# dr1_h.net
KiCad netlist of a schematic drawn in EAGLE
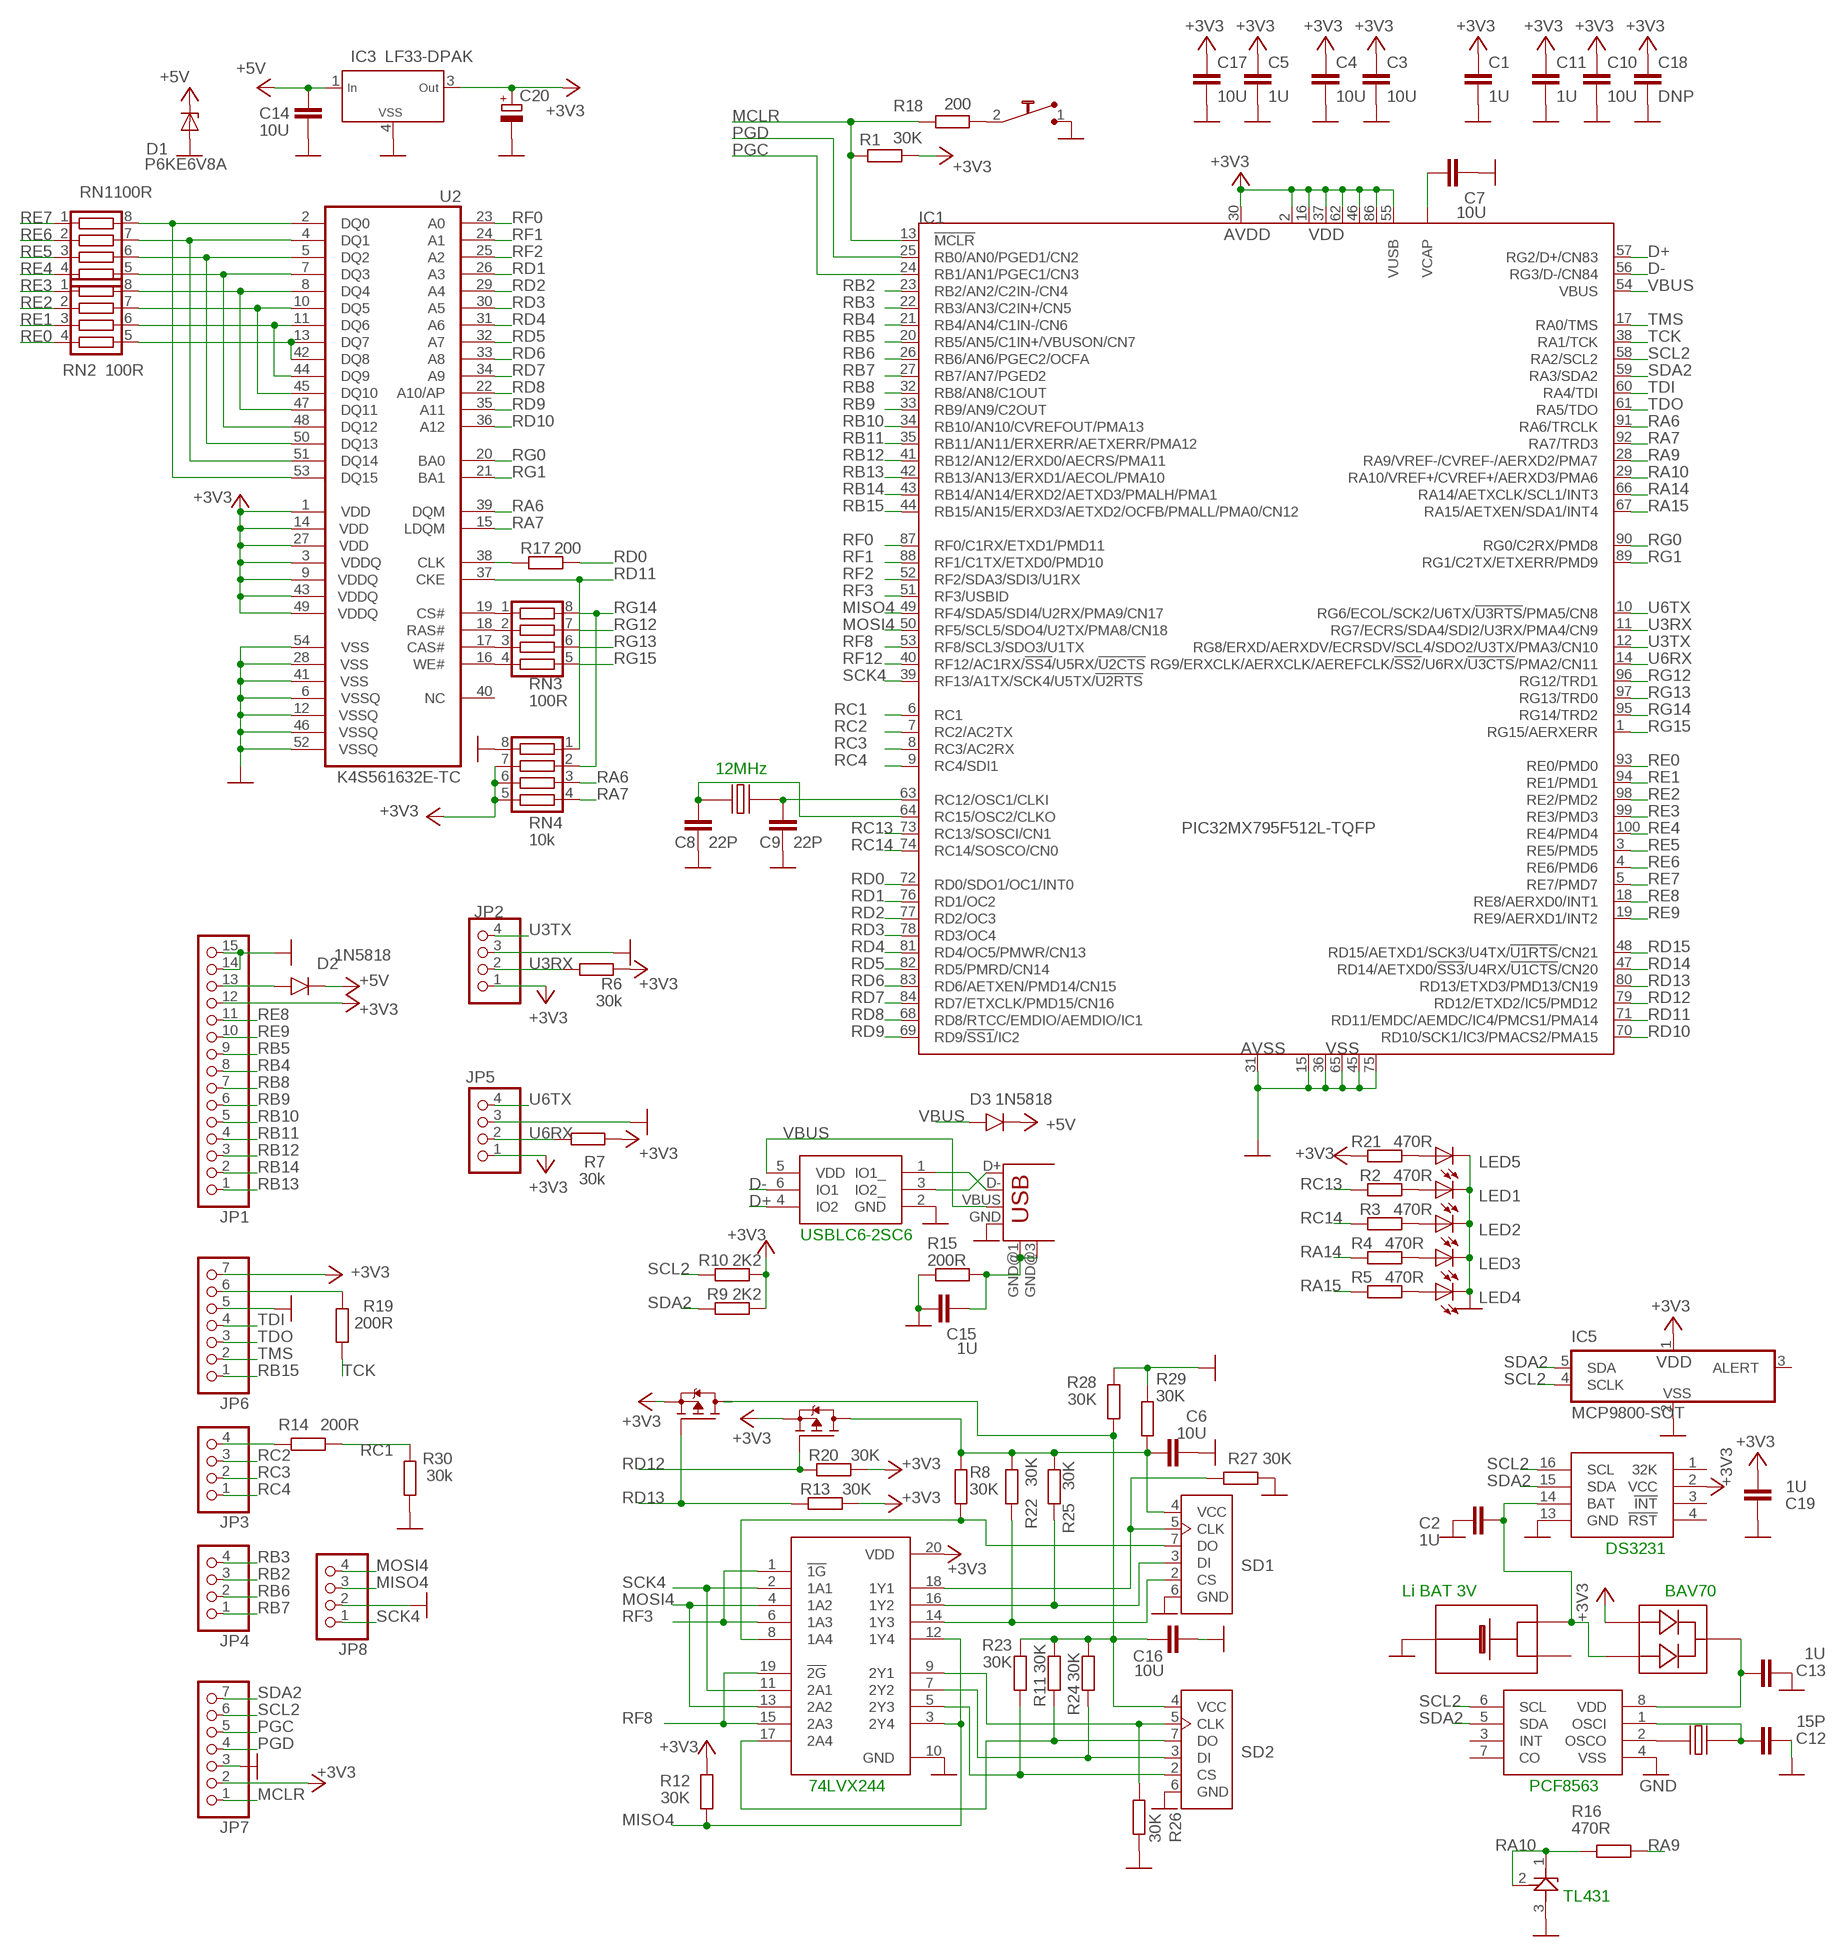
[diagram p0: schematic, sheet 1]

(export (version "E")
  (design (tool "Eeschema 10.0.6"))
  (components
    (comp (ref "1")
      (value "WE_TVS_2USB")
      (footprint "eagle-import:SOT23-6")
      (libsource (lib "eagle-import") (part "WE_TVS_2USB"))
    )
    (comp (ref "B1")
      (value "BATT_3001")
      (footprint "eagle-import:BATT_KEYS3001")
      (libsource (lib "eagle-import") (part "BATT_3001"))
    )
    (comp (ref "C1")
      (value "1U")
      (footprint "eagle-import:R0805")
      (libsource (lib "eagle-import") (part "C_0806"))
    )
    (comp (ref "C2")
      (value "1U")
      (footprint "eagle-import:R0805")
      (libsource (lib "eagle-import") (part "C_0806"))
    )
    (comp (ref "C3")
      (value "10U")
      (footprint "eagle-import:R0805")
      (libsource (lib "eagle-import") (part "C_0806"))
    )
    (comp (ref "C4")
      (value "10U")
      (footprint "eagle-import:R0805")
      (libsource (lib "eagle-import") (part "C_0806"))
    )
    (comp (ref "C5")
      (value "1U")
      (footprint "eagle-import:R0805")
      (libsource (lib "eagle-import") (part "C_0806"))
    )
    (comp (ref "C6")
      (value "10U")
      (footprint "eagle-import:R0805")
      (libsource (lib "eagle-import") (part "C_0806"))
    )
    (comp (ref "C7")
      (value "10U")
      (footprint "eagle-import:R0805")
      (libsource (lib "eagle-import") (part "C_0806"))
    )
    (comp (ref "C8")
      (value "22P")
      (footprint "eagle-import:0603")
      (libsource (lib "eagle-import") (part "C_0603"))
    )
    (comp (ref "C9")
      (value "22P")
      (footprint "eagle-import:0603")
      (libsource (lib "eagle-import") (part "C_0603"))
    )
    (comp (ref "C10")
      (value "10U")
      (footprint "eagle-import:R0805")
      (libsource (lib "eagle-import") (part "C_0806"))
    )
    (comp (ref "C11")
      (value "1U")
      (footprint "eagle-import:R0805")
      (libsource (lib "eagle-import") (part "C_0806"))
    )
    (comp (ref "C12")
      (value "15P")
      (footprint "eagle-import:R0805")
      (libsource (lib "eagle-import") (part "C_0806"))
    )
    (comp (ref "C13")
      (value "1U")
      (footprint "eagle-import:R0805")
      (libsource (lib "eagle-import") (part "C_0806"))
    )
    (comp (ref "C14")
      (value "10U")
      (footprint "eagle-import:R0805")
      (libsource (lib "eagle-import") (part "C_0806"))
    )
    (comp (ref "C15")
      (value "1U")
      (footprint "eagle-import:0603")
      (libsource (lib "eagle-import") (part "C_0603"))
    )
    (comp (ref "C16")
      (value "10U")
      (footprint "eagle-import:R0805")
      (libsource (lib "eagle-import") (part "C_0806"))
    )
    (comp (ref "C17")
      (value "10U")
      (footprint "eagle-import:R0805")
      (libsource (lib "eagle-import") (part "C_0806"))
    )
    (comp (ref "C18")
      (value "DNP")
      (footprint "eagle-import:R0805")
      (libsource (lib "eagle-import") (part "C_0806"))
    )
    (comp (ref "C19")
      (value "1U")
      (footprint "eagle-import:0603")
      (libsource (lib "eagle-import") (part "C_0603"))
    )
    (comp (ref "C20")
      (value "CPOL-EUSMCB")
      (footprint "eagle-import:SMC_B")
      (libsource (lib "eagle-import") (part "CPOL-EUSMCB"))
    )
    (comp (ref "D1")
      (value "P6KE6V8A")
      (footprint "eagle-import:SMB")
      (libsource (lib "eagle-import") (part "ZENER-DIODESMB"))
    )
    (comp (ref "D2")
      (value "1N5818")
      (footprint "eagle-import:SM-1")
      (libsource (lib "eagle-import") (part "1N4007-SM"))
    )
    (comp (ref "D3")
      (value "1N5818")
      (footprint "eagle-import:SM-1")
      (libsource (lib "eagle-import") (part "1N4007-SM"))
    )
    (comp (ref "IC1")
      (value "PIC32MX795F512L-TQFP")
      (footprint "eagle-import:TQFP100")
      (libsource (lib "eagle-import") (part "PIC32MX795F512L-TQFP"))
    )
    (comp (ref "IC2")
      (value "74244TSSOP20")
      (footprint "eagle-import:TSSOP20")
      (libsource (lib "eagle-import") (part "74244TSSOP20"))
    )
    (comp (ref "IC3")
      (value "LF33-DPAK")
      (footprint "eagle-import:DPAK")
      (libsource (lib "eagle-import") (part "LF33-DPAK"))
    )
    (comp (ref "IC4")
      (value "PCF8563_SO8")
      (footprint "eagle-import:SO-08")
      (libsource (lib "eagle-import") (part "PCF8563_SO8"))
    )
    (comp (ref "IC5")
      (value "MCP9800-SOT")
      (footprint "eagle-import:SOT23-5L")
      (libsource (lib "eagle-import") (part "MCP9800-SOT"))
    )
    (comp (ref "JP1")
      (value "PINHD-1X15_2.54-S")
      (footprint "eagle-import:1X15-S")
      (libsource (lib "eagle-import") (part "PINHD-1X15_2.54-S"))
    )
    (comp (ref "JP2")
      (value "PINHD-1X04_2.54-S")
      (footprint "eagle-import:1X04-S")
      (libsource (lib "eagle-import") (part "PINHD-1X04_2.54-S"))
    )
    (comp (ref "JP3")
      (value "PINHD-1X04_2.54-S")
      (footprint "eagle-import:1X04-S")
      (libsource (lib "eagle-import") (part "PINHD-1X04_2.54-S"))
    )
    (comp (ref "JP4")
      (value "PINHD-1X04_2.54-S")
      (footprint "eagle-import:1X04-S")
      (libsource (lib "eagle-import") (part "PINHD-1X04_2.54-S"))
    )
    (comp (ref "JP5")
      (value "PINHD-1X04_2.54-S")
      (footprint "eagle-import:1X04-S")
      (libsource (lib "eagle-import") (part "PINHD-1X04_2.54-S"))
    )
    (comp (ref "JP6")
      (value "PINHD-1X07_2.54-S")
      (footprint "eagle-import:1X07-S")
      (libsource (lib "eagle-import") (part "PINHD-1X07_2.54-S"))
    )
    (comp (ref "JP7")
      (value "PINHD-1X07_2.54-S")
      (footprint "eagle-import:1X07-S")
      (libsource (lib "eagle-import") (part "PINHD-1X07_2.54-S"))
    )
    (comp (ref "JP8")
      (value "PINHD-1X04_2.54-S")
      (footprint "eagle-import:1X04-S")
      (libsource (lib "eagle-import") (part "PINHD-1X04_2.54-S"))
    )
    (comp (ref "LED1")
      (value "LEDCHIPLED_0603")
      (footprint "eagle-import:CHIPLED_0603")
      (libsource (lib "eagle-import") (part "LEDCHIPLED_0603"))
    )
    (comp (ref "LED2")
      (value "LEDCHIPLED_0603")
      (footprint "eagle-import:CHIPLED_0603")
      (libsource (lib "eagle-import") (part "LEDCHIPLED_0603"))
    )
    (comp (ref "LED3")
      (value "LEDCHIPLED_0603")
      (footprint "eagle-import:CHIPLED_0603")
      (libsource (lib "eagle-import") (part "LEDCHIPLED_0603"))
    )
    (comp (ref "LED4")
      (value "LEDCHIPLED_0603")
      (footprint "eagle-import:CHIPLED_0603")
      (libsource (lib "eagle-import") (part "LEDCHIPLED_0603"))
    )
    (comp (ref "LED5")
      (value "LEDCHIPLED_0603")
      (footprint "eagle-import:CHIPLED_0603")
      (libsource (lib "eagle-import") (part "LEDCHIPLED_0603"))
    )
    (comp (ref "R1")
      (value "30K")
      (footprint "eagle-import:0603")
      (libsource (lib "eagle-import") (part "R_0603"))
    )
    (comp (ref "R2")
      (value "470R")
      (footprint "eagle-import:0603")
      (libsource (lib "eagle-import") (part "R_0603"))
    )
    (comp (ref "R3")
      (value "470R")
      (footprint "eagle-import:0603")
      (libsource (lib "eagle-import") (part "R_0603"))
    )
    (comp (ref "R4")
      (value "470R")
      (footprint "eagle-import:0603")
      (libsource (lib "eagle-import") (part "R_0603"))
    )
    (comp (ref "R5")
      (value "470R")
      (footprint "eagle-import:0603")
      (libsource (lib "eagle-import") (part "R_0603"))
    )
    (comp (ref "R6")
      (value "30k")
      (footprint "eagle-import:0603")
      (libsource (lib "eagle-import") (part "R_0603"))
    )
    (comp (ref "R7")
      (value "30k")
      (footprint "eagle-import:0603")
      (libsource (lib "eagle-import") (part "R_0603"))
    )
    (comp (ref "R8")
      (value "30K")
      (footprint "eagle-import:0603")
      (libsource (lib "eagle-import") (part "R_0603"))
    )
    (comp (ref "R9")
      (value "2K2")
      (footprint "eagle-import:0603")
      (libsource (lib "eagle-import") (part "R_0603"))
    )
    (comp (ref "R10")
      (value "2K2")
      (footprint "eagle-import:0603")
      (libsource (lib "eagle-import") (part "R_0603"))
    )
    (comp (ref "R11")
      (value "30K")
      (footprint "eagle-import:0603")
      (libsource (lib "eagle-import") (part "R_0603"))
    )
    (comp (ref "R12")
      (value "30K")
      (footprint "eagle-import:0603")
      (libsource (lib "eagle-import") (part "R_0603"))
    )
    (comp (ref "R13")
      (value "30K")
      (footprint "eagle-import:0603")
      (libsource (lib "eagle-import") (part "R_0603"))
    )
    (comp (ref "R14")
      (value "200R")
      (footprint "eagle-import:0603")
      (libsource (lib "eagle-import") (part "R_0603"))
    )
    (comp (ref "R15")
      (value "200R")
      (footprint "eagle-import:0603")
      (libsource (lib "eagle-import") (part "R_0603"))
    )
    (comp (ref "R16")
      (value "470R")
      (footprint "eagle-import:0603")
      (libsource (lib "eagle-import") (part "R_0603"))
    )
    (comp (ref "R17")
      (value "200")
      (footprint "eagle-import:0603")
      (libsource (lib "eagle-import") (part "R_0603"))
    )
    (comp (ref "R18")
      (value "200")
      (footprint "eagle-import:0603")
      (libsource (lib "eagle-import") (part "R_0603"))
    )
    (comp (ref "R19")
      (value "200R")
      (footprint "eagle-import:0603")
      (libsource (lib "eagle-import") (part "R_0603"))
    )
    (comp (ref "R20")
      (value "30K")
      (footprint "eagle-import:0603")
      (libsource (lib "eagle-import") (part "R_0603"))
    )
    (comp (ref "R21")
      (value "470R")
      (footprint "eagle-import:0603")
      (libsource (lib "eagle-import") (part "R_0603"))
    )
    (comp (ref "R22")
      (value "30K")
      (footprint "eagle-import:0603")
      (libsource (lib "eagle-import") (part "R_0603"))
    )
    (comp (ref "R23")
      (value "30K")
      (footprint "eagle-import:0603")
      (libsource (lib "eagle-import") (part "R_0603"))
    )
    (comp (ref "R24")
      (value "30K")
      (footprint "eagle-import:0603")
      (libsource (lib "eagle-import") (part "R_0603"))
    )
    (comp (ref "R25")
      (value "30K")
      (footprint "eagle-import:0603")
      (libsource (lib "eagle-import") (part "R_0603"))
    )
    (comp (ref "R26")
      (value "30K")
      (footprint "eagle-import:0603")
      (libsource (lib "eagle-import") (part "R_0603"))
    )
    (comp (ref "R27")
      (value "30K")
      (footprint "eagle-import:0603")
      (libsource (lib "eagle-import") (part "R_0603"))
    )
    (comp (ref "R28")
      (value "30K")
      (footprint "eagle-import:0603")
      (libsource (lib "eagle-import") (part "R_0603"))
    )
    (comp (ref "R29")
      (value "30K")
      (footprint "eagle-import:0603")
      (libsource (lib "eagle-import") (part "R_0603"))
    )
    (comp (ref "R30")
      (value "30k")
      (footprint "eagle-import:0603")
      (libsource (lib "eagle-import") (part "R_0603"))
    )
    (comp (ref "RN1")
      (value "100R")
      (footprint "eagle-import:CTS742C083")
      (libsource (lib "eagle-import") (part "CTS742C083"))
    )
    (comp (ref "RN2")
      (value "100R")
      (footprint "eagle-import:CTS742C083")
      (libsource (lib "eagle-import") (part "CTS742C083"))
    )
    (comp (ref "RN3")
      (value "100R")
      (footprint "eagle-import:CTS742C083")
      (libsource (lib "eagle-import") (part "CTS742C083"))
    )
    (comp (ref "RN4")
      (value "10k")
      (footprint "eagle-import:CTS742C083")
      (libsource (lib "eagle-import") (part "CTS742C083"))
    )
    (comp (ref "SD1")
      (value "SF-MICROSD")
      (footprint "eagle-import:MICROSD")
      (libsource (lib "eagle-import") (part "SF-MICROSD"))
    )
    (comp (ref "SD2")
      (value "SF-MICROSD")
      (footprint "eagle-import:MICROSD")
      (libsource (lib "eagle-import") (part "SF-MICROSD"))
    )
    (comp (ref "T1")
      (value "SI2333")
      (footprint "eagle-import:SOT23-3")
      (libsource (lib "eagle-import") (part "SI2333"))
    )
    (comp (ref "U$1")
      (value "TL431_SOT23")
      (footprint "eagle-import:SOT23")
      (libsource (lib "eagle-import") (part "TL431_SOT23"))
    )
    (comp (ref "U$2")
      (value "DS3231")
      (footprint "eagle-import:SO-16")
      (libsource (lib "eagle-import") (part "DS3231"))
    )
    (comp (ref "U$6")
      (value "BAV70")
      (footprint "eagle-import:SOT23")
      (libsource (lib "eagle-import") (part "BAV70"))
    )
    (comp (ref "U$8")
      (value "SWITCH_MINI")
      (footprint "eagle-import:SW_SMD_MINI")
      (libsource (lib "eagle-import") (part "SWITCH_MINI"))
    )
    (comp (ref "U$12")
      (value "SI2333")
      (footprint "eagle-import:SOT23-3")
      (libsource (lib "eagle-import") (part "SI2333"))
    )
    (comp (ref "U2")
      (value "K4S561632E-TC")
      (footprint "eagle-import:TSOP54")
      (libsource (lib "eagle-import") (part "K4S561632E-TC"))
    )
    (comp (ref "USB1")
      (value "USB-MB-S")
      (footprint "eagle-import:USB-MB-S")
      (libsource (lib "eagle-import") (part "USB-MB-S"))
    )
    (comp (ref "X1")
      (value "32768")
      (footprint "eagle-import:TC38")
      (libsource (lib "eagle-import") (part "CRYST_TC26TC38"))
    )
    (comp (ref "X2")
      (value "12MHz")
      (footprint "eagle-import:TC38")
      (libsource (lib "eagle-import") (part "CRYST_TC26TC38"))
    )
  )
  (nets
    (net (code "1") (name "+3V3") (class "Default")
      (node (ref "C1") (pin "1") (pinfunction "1_1") (pintype "passive"))
      (node (ref "C10") (pin "1") (pinfunction "1_1") (pintype "passive"))
      (node (ref "C11") (pin "1") (pinfunction "1_1") (pintype "passive"))
      (node (ref "C17") (pin "1") (pinfunction "1_1") (pintype "passive"))
      (node (ref "C18") (pin "1") (pinfunction "1_1") (pintype "passive"))
      (node (ref "C19") (pin "2") (pinfunction "2_2") (pintype "passive"))
      (node (ref "C20") (pin "+") (pinfunction "+_+") (pintype "passive"))
      (node (ref "C3") (pin "1") (pinfunction "1_1") (pintype "passive"))
      (node (ref "C4") (pin "1") (pinfunction "1_1") (pintype "passive"))
      (node (ref "C5") (pin "1") (pinfunction "1_1") (pintype "passive"))
      (node (ref "IC1") (pin "16") (pinfunction "VDD2_16") (pintype "power_in"))
      (node (ref "IC1") (pin "2") (pinfunction "VDD1_2") (pintype "power_in"))
      (node (ref "IC1") (pin "30") (pinfunction "AVDD_30") (pintype "power_in"))
      (node (ref "IC1") (pin "37") (pinfunction "VDD3_37") (pintype "power_in"))
      (node (ref "IC1") (pin "46") (pinfunction "VDD4_46") (pintype "power_in"))
      (node (ref "IC1") (pin "55") (pinfunction "VUSB_55") (pintype "bidirectional"))
      (node (ref "IC1") (pin "62") (pinfunction "VDD_62") (pintype "power_in"))
      (node (ref "IC1") (pin "86") (pinfunction "VDD5_86") (pintype "power_in"))
      (node (ref "IC2") (pin "20") (pinfunction "VDD_20") (pintype "bidirectional"))
      (node (ref "IC3") (pin "3") (pinfunction "OUT_3") (pintype "output"))
      (node (ref "IC5") (pin "1") (pinfunction "VDD_1") (pintype "power_in"))
      (node (ref "JP1") (pin "12") (pinfunction "12_12") (pintype "passive"))
      (node (ref "JP2") (pin "1") (pinfunction "1_1") (pintype "passive"))
      (node (ref "JP5") (pin "1") (pinfunction "1_1") (pintype "passive"))
      (node (ref "JP6") (pin "7") (pinfunction "7_7") (pintype "passive"))
      (node (ref "JP7") (pin "2") (pinfunction "2_2") (pintype "passive"))
      (node (ref "R1") (pin "2") (pinfunction "2_2") (pintype "passive"))
      (node (ref "R10") (pin "2") (pinfunction "2_2") (pintype "passive"))
      (node (ref "R12") (pin "2") (pinfunction "2_2") (pintype "passive"))
      (node (ref "R13") (pin "1") (pinfunction "1_1") (pintype "passive"))
      (node (ref "R20") (pin "2") (pinfunction "2_2") (pintype "passive"))
      (node (ref "R21") (pin "1") (pinfunction "1_1") (pintype "passive"))
      (node (ref "R6") (pin "1") (pinfunction "1_1") (pintype "passive"))
      (node (ref "R7") (pin "1") (pinfunction "1_1") (pintype "passive"))
      (node (ref "R9") (pin "2") (pinfunction "2_2") (pintype "passive"))
      (node (ref "RN4") (pin "5") (pinfunction "5_5") (pintype "passive"))
      (node (ref "RN4") (pin "6") (pinfunction "6_6") (pintype "passive"))
      (node (ref "RN4") (pin "7") (pinfunction "7_7") (pintype "passive"))
      (node (ref "T1") (pin "2") (pinfunction "S_2") (pintype "passive"))
      (node (ref "U$12") (pin "2") (pinfunction "S_2") (pintype "passive"))
      (node (ref "U$2") (pin "2") (pinfunction "VCC_2") (pintype "bidirectional"))
      (node (ref "U$6") (pin "1") (pinfunction "A1_1") (pintype "bidirectional"))
      (node (ref "U2") (pin "1") (pinfunction "VDD_1") (pintype "power_in"))
      (node (ref "U2") (pin "14") (pinfunction "VDD_14") (pintype "power_in"))
      (node (ref "U2") (pin "27") (pinfunction "VDD_27") (pintype "power_in"))
      (node (ref "U2") (pin "3") (pinfunction "VDDQ_3") (pintype "power_in"))
      (node (ref "U2") (pin "43") (pinfunction "VDDQ_43") (pintype "power_in"))
      (node (ref "U2") (pin "49") (pinfunction "VDDQ_49") (pintype "power_in"))
      (node (ref "U2") (pin "9") (pinfunction "VDDQ_9") (pintype "power_in"))
    )
    (net (code "2") (name "+5V") (class "Default")
      (node (ref "C14") (pin "1") (pinfunction "1_1") (pintype "passive"))
      (node (ref "D1") (pin "C") (pinfunction "C_C") (pintype "passive"))
      (node (ref "D2") (pin "K") (pinfunction "K_K") (pintype "output"))
      (node (ref "D3") (pin "K") (pinfunction "K_K") (pintype "output"))
      (node (ref "IC3") (pin "1") (pinfunction "IN_1") (pintype "input"))
    )
    (net (code "3") (name "/D+") (class "Default")
      (node (ref "1") (pin "4") (pinfunction "IO2_4") (pintype "bidirectional"))
      (node (ref "IC1") (pin "57") (pinfunction "RG2/D+/CN83_57") (pintype "bidirectional"))
    )
    (net (code "4") (name "/D-") (class "Default")
      (node (ref "1") (pin "6") (pinfunction "IO1_6") (pintype "bidirectional"))
      (node (ref "IC1") (pin "56") (pinfunction "RG3/D-/CN84_56") (pintype "bidirectional"))
    )
    (net (code "5") (name "/MCLR") (class "Default")
      (node (ref "IC1") (pin "13") (pinfunction "~{MCLR}_13") (pintype "bidirectional"))
      (node (ref "JP7") (pin "1") (pinfunction "1_1") (pintype "passive"))
      (node (ref "R1") (pin "1") (pinfunction "1_1") (pintype "passive"))
      (node (ref "R18") (pin "1") (pinfunction "1_1") (pintype "passive"))
    )
    (net (code "6") (name "/MISO4") (class "Default")
      (node (ref "IC1") (pin "49") (pinfunction "RF4/SDA5/SDI4/U2RX/PMA9/CN17_49") (pintype "bidirectional"))
      (node (ref "IC2") (pin "12") (pinfunction "1Y4_12") (pintype "bidirectional"))
      (node (ref "IC2") (pin "3") (pinfunction "2Y4_3") (pintype "bidirectional"))
      (node (ref "JP8") (pin "3") (pinfunction "3_3") (pintype "passive"))
      (node (ref "R12") (pin "1") (pinfunction "1_1") (pintype "passive"))
    )
    (net (code "7") (name "/MOSI4") (class "Default")
      (node (ref "IC1") (pin "50") (pinfunction "RF5/SCL5/SDO4/U2TX/PMA8/CN18_50") (pintype "bidirectional"))
      (node (ref "IC2") (pin "13") (pinfunction "2A2_13") (pintype "bidirectional"))
      (node (ref "IC2") (pin "4") (pinfunction "1A2_4") (pintype "bidirectional"))
      (node (ref "JP8") (pin "4") (pinfunction "4_4") (pintype "passive"))
    )
    (net (code "8") (name "/PGC") (class "Default")
      (node (ref "IC1") (pin "24") (pinfunction "RB1/AN1/PGEC1/CN3_24") (pintype "bidirectional"))
      (node (ref "JP7") (pin "5") (pinfunction "5_5") (pintype "passive"))
    )
    (net (code "9") (name "/PGD") (class "Default")
      (node (ref "IC1") (pin "25") (pinfunction "RB0/AN0/PGED1/CN2_25") (pintype "bidirectional"))
      (node (ref "JP7") (pin "4") (pinfunction "4_4") (pintype "passive"))
    )
    (net (code "10") (name "/RA6") (class "Default")
      (node (ref "IC1") (pin "91") (pinfunction "RA6/TRCLK_91") (pintype "bidirectional"))
      (node (ref "RN4") (pin "3") (pinfunction "3_3") (pintype "passive"))
      (node (ref "U2") (pin "39") (pinfunction "DQM_39") (pintype "input"))
    )
    (net (code "11") (name "/RA7") (class "Default")
      (node (ref "IC1") (pin "92") (pinfunction "RA7/TRD3_92") (pintype "bidirectional"))
      (node (ref "RN4") (pin "4") (pinfunction "4_4") (pintype "passive"))
      (node (ref "U2") (pin "15") (pinfunction "LDQM_15") (pintype "input"))
    )
    (net (code "12") (name "/RA9") (class "Default")
      (node (ref "IC1") (pin "28") (pinfunction "RA9/VREF-/CVREF-/AERXD2/PMA7_28") (pintype "bidirectional"))
      (node (ref "R16") (pin "2") (pinfunction "2_2") (pintype "passive"))
    )
    (net (code "13") (name "/RA10") (class "Default")
      (node (ref "IC1") (pin "29") (pinfunction "RA10/VREF+/CVREF+/AERXD3/PMA6_29") (pintype "bidirectional"))
      (node (ref "R16") (pin "1") (pinfunction "1_1") (pintype "passive"))
      (node (ref "U$1") (pin "1") (pinfunction "C_1") (pintype "bidirectional"))
      (node (ref "U$1") (pin "2") (pinfunction "R_2") (pintype "bidirectional"))
    )
    (net (code "14") (name "/RA14") (class "Default")
      (node (ref "IC1") (pin "66") (pinfunction "RA14/AETXCLK/SCL1/INT3_66") (pintype "bidirectional"))
      (node (ref "R4") (pin "1") (pinfunction "1_1") (pintype "passive"))
    )
    (net (code "15") (name "/RA15") (class "Default")
      (node (ref "IC1") (pin "67") (pinfunction "RA15/AETXEN/SDA1/INT4_67") (pintype "bidirectional"))
      (node (ref "R5") (pin "1") (pinfunction "1_1") (pintype "passive"))
    )
    (net (code "16") (name "/RB2") (class "Default")
      (node (ref "IC1") (pin "23") (pinfunction "RB2/AN2/C2IN-/CN4_23") (pintype "bidirectional"))
      (node (ref "JP4") (pin "3") (pinfunction "3_3") (pintype "passive"))
    )
    (net (code "17") (name "/RB3") (class "Default")
      (node (ref "IC1") (pin "22") (pinfunction "RB3/AN3/C2IN+/CN5_22") (pintype "bidirectional"))
      (node (ref "JP4") (pin "4") (pinfunction "4_4") (pintype "passive"))
    )
    (net (code "18") (name "/RB4") (class "Default")
      (node (ref "IC1") (pin "21") (pinfunction "RB4/AN4/C1IN-/CN6_21") (pintype "bidirectional"))
      (node (ref "JP1") (pin "8") (pinfunction "8_8") (pintype "passive"))
    )
    (net (code "19") (name "/RB5") (class "Default")
      (node (ref "IC1") (pin "20") (pinfunction "RB5/AN5/C1IN+/VBUSON/CN7_20") (pintype "bidirectional"))
      (node (ref "JP1") (pin "9") (pinfunction "9_9") (pintype "passive"))
    )
    (net (code "20") (name "/RB6") (class "Default")
      (node (ref "IC1") (pin "26") (pinfunction "RB6/AN6/PGEC2/OCFA_26") (pintype "bidirectional"))
      (node (ref "JP4") (pin "2") (pinfunction "2_2") (pintype "passive"))
    )
    (net (code "21") (name "/RB7") (class "Default")
      (node (ref "IC1") (pin "27") (pinfunction "RB7/AN7/PGED2_27") (pintype "bidirectional"))
      (node (ref "JP4") (pin "1") (pinfunction "1_1") (pintype "passive"))
    )
    (net (code "22") (name "/RB8") (class "Default")
      (node (ref "IC1") (pin "32") (pinfunction "RB8/AN8/C1OUT_32") (pintype "bidirectional"))
      (node (ref "JP1") (pin "7") (pinfunction "7_7") (pintype "passive"))
    )
    (net (code "23") (name "/RB9") (class "Default")
      (node (ref "IC1") (pin "33") (pinfunction "RB9/AN9/C2OUT_33") (pintype "bidirectional"))
      (node (ref "JP1") (pin "6") (pinfunction "6_6") (pintype "passive"))
    )
    (net (code "24") (name "/RB10") (class "Default")
      (node (ref "IC1") (pin "34") (pinfunction "RB10/AN10/CVREFOUT/PMA13_34") (pintype "bidirectional"))
      (node (ref "JP1") (pin "5") (pinfunction "5_5") (pintype "passive"))
    )
    (net (code "25") (name "/RB11") (class "Default")
      (node (ref "IC1") (pin "35") (pinfunction "RB11/AN11/ERXERR/AETXERR/PMA12_35") (pintype "bidirectional"))
      (node (ref "JP1") (pin "4") (pinfunction "4_4") (pintype "passive"))
    )
    (net (code "26") (name "/RB12") (class "Default")
      (node (ref "IC1") (pin "41") (pinfunction "RB12/AN12/ERXD0/AECRS/PMA11_41") (pintype "bidirectional"))
      (node (ref "JP1") (pin "3") (pinfunction "3_3") (pintype "passive"))
    )
    (net (code "27") (name "/RB13") (class "Default")
      (node (ref "IC1") (pin "42") (pinfunction "RB13/AN13/ERXD1/AECOL/PMA10_42") (pintype "bidirectional"))
      (node (ref "JP1") (pin "1") (pinfunction "1_1") (pintype "passive"))
    )
    (net (code "28") (name "/RB14") (class "Default")
      (node (ref "IC1") (pin "43") (pinfunction "RB14/AN14/ERXD2/AETXD3/PMALH/PMA1_43") (pintype "bidirectional"))
      (node (ref "JP1") (pin "2") (pinfunction "2_2") (pintype "passive"))
    )
    (net (code "29") (name "/RB15") (class "Default")
      (node (ref "IC1") (pin "44") (pinfunction "RB15/AN15/ERXD3/AETXD2/OCFB/PMALL/PMA0/CN12_44") (pintype "bidirectional"))
      (node (ref "JP6") (pin "1") (pinfunction "1_1") (pintype "passive"))
    )
    (net (code "30") (name "/RC1") (class "Default")
      (node (ref "IC1") (pin "6") (pinfunction "RC1_6") (pintype "bidirectional"))
      (node (ref "R14") (pin "1") (pinfunction "1_1") (pintype "passive"))
      (node (ref "R30") (pin "2") (pinfunction "2_2") (pintype "passive"))
    )
    (net (code "31") (name "/RC2") (class "Default")
      (node (ref "IC1") (pin "7") (pinfunction "RC2/AC2TX_7") (pintype "bidirectional"))
      (node (ref "JP3") (pin "3") (pinfunction "3_3") (pintype "passive"))
    )
    (net (code "32") (name "/RC3") (class "Default")
      (node (ref "IC1") (pin "8") (pinfunction "RC3/AC2RX_8") (pintype "bidirectional"))
      (node (ref "JP3") (pin "2") (pinfunction "2_2") (pintype "passive"))
    )
    (net (code "33") (name "/RC4") (class "Default")
      (node (ref "IC1") (pin "9") (pinfunction "RC4/SDI1_9") (pintype "bidirectional"))
      (node (ref "JP3") (pin "1") (pinfunction "1_1") (pintype "passive"))
    )
    (net (code "34") (name "/RC13") (class "Default")
      (node (ref "IC1") (pin "73") (pinfunction "RC13/SOSCI/CN1_73") (pintype "bidirectional"))
      (node (ref "R2") (pin "1") (pinfunction "1_1") (pintype "passive"))
    )
    (net (code "35") (name "/RC14") (class "Default")
      (node (ref "IC1") (pin "74") (pinfunction "RC14/SOSCO/CN0_74") (pintype "bidirectional"))
      (node (ref "R3") (pin "1") (pinfunction "1_1") (pintype "passive"))
    )
    (net (code "36") (name "/RD0") (class "Default")
      (node (ref "IC1") (pin "72") (pinfunction "RD0/SDO1/OC1/INT0_72") (pintype "bidirectional"))
      (node (ref "R17") (pin "2") (pinfunction "2_2") (pintype "passive"))
    )
    (net (code "37") (name "/RD1") (class "Default")
      (node (ref "IC1") (pin "76") (pinfunction "RD1/OC2_76") (pintype "bidirectional"))
      (node (ref "U2") (pin "26") (pinfunction "A3_26") (pintype "input"))
    )
    (net (code "38") (name "/RD2") (class "Default")
      (node (ref "IC1") (pin "77") (pinfunction "RD2/OC3_77") (pintype "bidirectional"))
      (node (ref "U2") (pin "29") (pinfunction "A4_29") (pintype "input"))
    )
    (net (code "39") (name "/RD3") (class "Default")
      (node (ref "IC1") (pin "78") (pinfunction "RD3/OC4_78") (pintype "bidirectional"))
      (node (ref "U2") (pin "30") (pinfunction "A5_30") (pintype "input"))
    )
    (net (code "40") (name "/RD4") (class "Default")
      (node (ref "IC1") (pin "81") (pinfunction "RD4/OC5/PMWR/CN13_81") (pintype "bidirectional"))
      (node (ref "U2") (pin "31") (pinfunction "A6_31") (pintype "input"))
    )
    (net (code "41") (name "/RD5") (class "Default")
      (node (ref "IC1") (pin "82") (pinfunction "RD5/PMRD/CN14_82") (pintype "bidirectional"))
      (node (ref "U2") (pin "32") (pinfunction "A7_32") (pintype "input"))
    )
    (net (code "42") (name "/RD6") (class "Default")
      (node (ref "IC1") (pin "83") (pinfunction "RD6/AETXEN/PMD14/CN15_83") (pintype "bidirectional"))
      (node (ref "U2") (pin "33") (pinfunction "A8_33") (pintype "input"))
    )
    (net (code "43") (name "/RD7") (class "Default")
      (node (ref "IC1") (pin "84") (pinfunction "RD7/ETXCLK/PMD15/CN16_84") (pintype "bidirectional"))
      (node (ref "U2") (pin "34") (pinfunction "A9_34") (pintype "input"))
    )
    (net (code "44") (name "/RD8") (class "Default")
      (node (ref "IC1") (pin "68") (pinfunction "RD8/RTCC/EMDIO/AEMDIO/IC1_68") (pintype "bidirectional"))
      (node (ref "U2") (pin "22") (pinfunction "A10/AP_22") (pintype "input"))
    )
    (net (code "45") (name "/RD9") (class "Default")
      (node (ref "IC1") (pin "69") (pinfunction "RD9/~{SS1}/IC2_69") (pintype "bidirectional"))
      (node (ref "U2") (pin "35") (pinfunction "A11_35") (pintype "input"))
    )
    (net (code "46") (name "/RD10") (class "Default")
      (node (ref "IC1") (pin "70") (pinfunction "RD10/SCK1/IC3/PMACS2/PMA15_70") (pintype "bidirectional"))
      (node (ref "U2") (pin "36") (pinfunction "A12_36") (pintype "input"))
    )
    (net (code "47") (name "/RD11") (class "Default")
      (node (ref "IC1") (pin "71") (pinfunction "RD11/EMDC/AEMDC/IC4/PMCS1/PMA14_71") (pintype "bidirectional"))
      (node (ref "RN4") (pin "1") (pinfunction "1_1") (pintype "passive"))
      (node (ref "U2") (pin "37") (pinfunction "CKE_37") (pintype "input"))
    )
    (net (code "48") (name "/RD12") (class "Default")
      (node (ref "IC1") (pin "79") (pinfunction "RD12/ETXD2/IC5/PMD12_79") (pintype "bidirectional"))
      (node (ref "R20") (pin "1") (pinfunction "1_1") (pintype "passive"))
      (node (ref "U$12") (pin "1") (pinfunction "G_1") (pintype "passive"))
    )
    (net (code "49") (name "/RD13") (class "Default")
      (node (ref "IC1") (pin "80") (pinfunction "RD13/ETXD3/PMD13/CN19_80") (pintype "bidirectional"))
      (node (ref "R13") (pin "2") (pinfunction "2_2") (pintype "passive"))
      (node (ref "T1") (pin "1") (pinfunction "G_1") (pintype "passive"))
    )
    (net (code "50") (name "/RD14") (class "Default")
      (node (ref "IC1") (pin "47") (pinfunction "RD14/AETXD0/~{SS3}/U4RX/~{U1CTS}/CN20_47") (pintype "bidirectional"))
    )
    (net (code "51") (name "/RD15") (class "Default")
      (node (ref "IC1") (pin "48") (pinfunction "RD15/AETXD1/SCK3/U4TX/~{U1RTS}/CN21_48") (pintype "bidirectional"))
    )
    (net (code "52") (name "/RE0") (class "Default")
      (node (ref "IC1") (pin "93") (pinfunction "RE0/PMD0_93") (pintype "bidirectional"))
      (node (ref "RN2") (pin "4") (pinfunction "4_4") (pintype "passive"))
    )
    (net (code "53") (name "/RE1") (class "Default")
      (node (ref "IC1") (pin "94") (pinfunction "RE1/PMD1_94") (pintype "bidirectional"))
      (node (ref "RN2") (pin "3") (pinfunction "3_3") (pintype "passive"))
    )
    (net (code "54") (name "/RE2") (class "Default")
      (node (ref "IC1") (pin "98") (pinfunction "RE2/PMD2_98") (pintype "bidirectional"))
      (node (ref "RN2") (pin "2") (pinfunction "2_2") (pintype "passive"))
    )
    (net (code "55") (name "/RE3") (class "Default")
      (node (ref "IC1") (pin "99") (pinfunction "RE3/PMD3_99") (pintype "bidirectional"))
      (node (ref "RN2") (pin "1") (pinfunction "1_1") (pintype "passive"))
    )
    (net (code "56") (name "/RE4") (class "Default")
      (node (ref "IC1") (pin "100") (pinfunction "RE4/PMD4_100") (pintype "bidirectional"))
      (node (ref "RN1") (pin "4") (pinfunction "4_4") (pintype "passive"))
    )
    (net (code "57") (name "/RE5") (class "Default")
      (node (ref "IC1") (pin "3") (pinfunction "RE5/PMD5_3") (pintype "bidirectional"))
      (node (ref "RN1") (pin "3") (pinfunction "3_3") (pintype "passive"))
    )
    (net (code "58") (name "/RE6") (class "Default")
      (node (ref "IC1") (pin "4") (pinfunction "RE6/PMD6_4") (pintype "bidirectional"))
      (node (ref "RN1") (pin "2") (pinfunction "2_2") (pintype "passive"))
    )
    (net (code "59") (name "/RE7") (class "Default")
      (node (ref "IC1") (pin "5") (pinfunction "RE7/PMD7_5") (pintype "bidirectional"))
      (node (ref "RN1") (pin "1") (pinfunction "1_1") (pintype "passive"))
    )
    (net (code "60") (name "/RE8") (class "Default")
      (node (ref "IC1") (pin "18") (pinfunction "RE8/AERXD0/INT1_18") (pintype "bidirectional"))
      (node (ref "JP1") (pin "11") (pinfunction "11_11") (pintype "passive"))
    )
    (net (code "61") (name "/RE9") (class "Default")
      (node (ref "IC1") (pin "19") (pinfunction "RE9/AERXD1/INT2_19") (pintype "bidirectional"))
      (node (ref "JP1") (pin "10") (pinfunction "10_10") (pintype "passive"))
    )
    (net (code "62") (name "/RF0") (class "Default")
      (node (ref "IC1") (pin "87") (pinfunction "RF0/C1RX/ETXD1/PMD11_87") (pintype "bidirectional"))
      (node (ref "U2") (pin "23") (pinfunction "A0_23") (pintype "input"))
    )
    (net (code "63") (name "/RF1") (class "Default")
      (node (ref "IC1") (pin "88") (pinfunction "RF1/C1TX/ETXD0/PMD10_88") (pintype "bidirectional"))
      (node (ref "U2") (pin "24") (pinfunction "A1_24") (pintype "input"))
    )
    (net (code "64") (name "/RF2") (class "Default")
      (node (ref "IC1") (pin "52") (pinfunction "RF2/SDA3/SDI3/U1RX_52") (pintype "bidirectional"))
      (node (ref "U2") (pin "25") (pinfunction "A2_25") (pintype "input"))
    )
    (net (code "65") (name "/RF3") (class "Default")
      (node (ref "IC1") (pin "51") (pinfunction "RF3/USBID_51") (pintype "bidirectional"))
      (node (ref "IC2") (pin "1") (pinfunction "~{1G}_1") (pintype "bidirectional"))
      (node (ref "IC2") (pin "6") (pinfunction "1A3_6") (pintype "bidirectional"))
    )
    (net (code "66") (name "/RF8") (class "Default")
      (node (ref "IC1") (pin "53") (pinfunction "RF8/SCL3/SDO3/U1TX_53") (pintype "bidirectional"))
      (node (ref "IC2") (pin "15") (pinfunction "2A3_15") (pintype "bidirectional"))
      (node (ref "IC2") (pin "19") (pinfunction "~{2G}_19") (pintype "bidirectional"))
    )
    (net (code "67") (name "/RF12") (class "Default")
      (node (ref "IC1") (pin "40") (pinfunction "RF12/AC1RX/~{SS4}/U5RX/~{U2CTS}_40") (pintype "bidirectional"))
    )
    (net (code "68") (name "/RG0") (class "Default")
      (node (ref "IC1") (pin "90") (pinfunction "RG0/C2RX/PMD8_90") (pintype "bidirectional"))
      (node (ref "U2") (pin "20") (pinfunction "BA0_20") (pintype "input"))
    )
    (net (code "69") (name "/RG1") (class "Default")
      (node (ref "IC1") (pin "89") (pinfunction "RG1/C2TX/ETXERR/PMD9_89") (pintype "bidirectional"))
      (node (ref "U2") (pin "21") (pinfunction "BA1_21") (pintype "input"))
    )
    (net (code "70") (name "/RG12") (class "Default")
      (node (ref "IC1") (pin "96") (pinfunction "RG12/TRD1_96") (pintype "bidirectional"))
      (node (ref "RN3") (pin "7") (pinfunction "7_7") (pintype "passive"))
    )
    (net (code "71") (name "/RG13") (class "Default")
      (node (ref "IC1") (pin "97") (pinfunction "RG13/TRD0_97") (pintype "bidirectional"))
      (node (ref "RN3") (pin "6") (pinfunction "6_6") (pintype "passive"))
    )
    (net (code "72") (name "/RG14") (class "Default")
      (node (ref "IC1") (pin "95") (pinfunction "RG14/TRD2_95") (pintype "bidirectional"))
      (node (ref "RN3") (pin "8") (pinfunction "8_8") (pintype "passive"))
      (node (ref "RN4") (pin "2") (pinfunction "2_2") (pintype "passive"))
    )
    (net (code "73") (name "/RG15") (class "Default")
      (node (ref "IC1") (pin "1") (pinfunction "RG15/AERXERR_1") (pintype "bidirectional"))
      (node (ref "RN3") (pin "5") (pinfunction "5_5") (pintype "passive"))
    )
    (net (code "74") (name "/SCK4") (class "Default")
      (node (ref "IC1") (pin "39") (pinfunction "RF13/A1TX/SCK4/U5TX/~{U2RTS}_39") (pintype "bidirectional"))
      (node (ref "IC2") (pin "11") (pinfunction "2A1_11") (pintype "bidirectional"))
      (node (ref "IC2") (pin "2") (pinfunction "1A1_2") (pintype "bidirectional"))
      (node (ref "JP8") (pin "1") (pinfunction "1_1") (pintype "passive"))
    )
    (net (code "75") (name "/SCL2") (class "Default")
      (node (ref "IC1") (pin "58") (pinfunction "RA2/SCL2_58") (pintype "bidirectional"))
      (node (ref "IC4") (pin "6") (pinfunction "SCL_6") (pintype "bidirectional"))
      (node (ref "IC5") (pin "4") (pinfunction "SCLK_4") (pintype "bidirectional"))
      (node (ref "JP7") (pin "6") (pinfunction "6_6") (pintype "passive"))
      (node (ref "R10") (pin "1") (pinfunction "1_1") (pintype "passive"))
      (node (ref "U$2") (pin "16") (pinfunction "SCL_16") (pintype "bidirectional"))
    )
    (net (code "76") (name "/SDA2") (class "Default")
      (node (ref "IC1") (pin "59") (pinfunction "RA3/SDA2_59") (pintype "bidirectional"))
      (node (ref "IC4") (pin "5") (pinfunction "SDA_5") (pintype "bidirectional"))
      (node (ref "IC5") (pin "5") (pinfunction "SDA_5") (pintype "bidirectional"))
      (node (ref "JP7") (pin "7") (pinfunction "7_7") (pintype "passive"))
      (node (ref "R9") (pin "1") (pinfunction "1_1") (pintype "passive"))
      (node (ref "U$2") (pin "15") (pinfunction "SDA_15") (pintype "bidirectional"))
    )
    (net (code "77") (name "/TCK") (class "Default")
      (node (ref "IC1") (pin "38") (pinfunction "RA1/TCK_38") (pintype "bidirectional"))
      (node (ref "R19") (pin "1") (pinfunction "1_1") (pintype "passive"))
    )
    (net (code "78") (name "/TDI") (class "Default")
      (node (ref "IC1") (pin "60") (pinfunction "RA4/TDI_60") (pintype "bidirectional"))
      (node (ref "JP6") (pin "4") (pinfunction "4_4") (pintype "passive"))
    )
    (net (code "79") (name "/TDO") (class "Default")
      (node (ref "IC1") (pin "61") (pinfunction "RA5/TDO_61") (pintype "bidirectional"))
      (node (ref "JP6") (pin "3") (pinfunction "3_3") (pintype "passive"))
    )
    (net (code "80") (name "/TMS") (class "Default")
      (node (ref "IC1") (pin "17") (pinfunction "RA0/TMS_17") (pintype "bidirectional"))
      (node (ref "JP6") (pin "2") (pinfunction "2_2") (pintype "passive"))
    )
    (net (code "81") (name "/U3RX") (class "Default")
      (node (ref "IC1") (pin "11") (pinfunction "RG7/ECRS/SDA4/SDI2/U3RX/PMA4/CN9_11") (pintype "bidirectional"))
      (node (ref "JP2") (pin "2") (pinfunction "2_2") (pintype "passive"))
      (node (ref "R6") (pin "2") (pinfunction "2_2") (pintype "passive"))
    )
    (net (code "82") (name "/U3TX") (class "Default")
      (node (ref "IC1") (pin "12") (pinfunction "RG8/ERXD/AERXDV/ECRSDV/SCL4/SDO2/U3TX/PMA3/CN10_12") (pintype "bidirectional"))
      (node (ref "JP2") (pin "4") (pinfunction "4_4") (pintype "passive"))
    )
    (net (code "83") (name "/U6RX") (class "Default")
      (node (ref "IC1") (pin "14") (pinfunction "RG9/ERXCLK/AERXCLK/AEREFCLK/~{SS2}/U6RX/~{U3CTS}/PMA2/CN11_14") (pintype "bidirectional"))
      (node (ref "JP5") (pin "2") (pinfunction "2_2") (pintype "passive"))
      (node (ref "R7") (pin "2") (pinfunction "2_2") (pintype "passive"))
    )
    (net (code "84") (name "/U6TX") (class "Default")
      (node (ref "IC1") (pin "10") (pinfunction "RG6/ECOL/SCK2/U6TX/~{U3RTS}/PMA5/CN8_10") (pintype "bidirectional"))
      (node (ref "JP5") (pin "4") (pinfunction "4_4") (pintype "passive"))
    )
    (net (code "85") (name "/VBUS") (class "Default")
      (node (ref "1") (pin "5") (pinfunction "VDD_5") (pintype "bidirectional"))
      (node (ref "D3") (pin "A") (pinfunction "A_A") (pintype "input"))
      (node (ref "IC1") (pin "54") (pinfunction "VBUS_54") (pintype "bidirectional"))
      (node (ref "USB1") (pin "VBUS") (pinfunction "VBUS_VBUS") (pintype "bidirectional"))
    )
    (net (code "86") (name "GND") (class "Default")
      (node (ref "1") (pin "2") (pinfunction "GND_2") (pintype "bidirectional"))
      (node (ref "B1") (pin "NEG") (pinfunction "NEG_NEG") (pintype "bidirectional"))
      (node (ref "C1") (pin "2") (pinfunction "2_2") (pintype "passive"))
      (node (ref "C10") (pin "2") (pinfunction "2_2") (pintype "passive"))
      (node (ref "C11") (pin "2") (pinfunction "2_2") (pintype "passive"))
      (node (ref "C12") (pin "2") (pinfunction "2_2") (pintype "passive"))
      (node (ref "C13") (pin "2") (pinfunction "2_2") (pintype "passive"))
      (node (ref "C14") (pin "2") (pinfunction "2_2") (pintype "passive"))
      (node (ref "C15") (pin "1") (pinfunction "1_1") (pintype "passive"))
      (node (ref "C16") (pin "2") (pinfunction "2_2") (pintype "passive"))
      (node (ref "C17") (pin "2") (pinfunction "2_2") (pintype "passive"))
      (node (ref "C18") (pin "2") (pinfunction "2_2") (pintype "passive"))
      (node (ref "C19") (pin "1") (pinfunction "1_1") (pintype "passive"))
      (node (ref "C2") (pin "2") (pinfunction "2_2") (pintype "passive"))
      (node (ref "C20") (pin "-") (pinfunction "-_-") (pintype "passive"))
      (node (ref "C3") (pin "2") (pinfunction "2_2") (pintype "passive"))
      (node (ref "C4") (pin "2") (pinfunction "2_2") (pintype "passive"))
      (node (ref "C5") (pin "2") (pinfunction "2_2") (pintype "passive"))
      (node (ref "C6") (pin "2") (pinfunction "2_2") (pintype "passive"))
      (node (ref "C7") (pin "2") (pinfunction "2_2") (pintype "passive"))
      (node (ref "C8") (pin "2") (pinfunction "2_2") (pintype "passive"))
      (node (ref "C9") (pin "2") (pinfunction "2_2") (pintype "passive"))
      (node (ref "D1") (pin "A") (pinfunction "A_A") (pintype "passive"))
      (node (ref "IC1") (pin "15") (pinfunction "VSS1_15") (pintype "power_in"))
      (node (ref "IC1") (pin "31") (pinfunction "AVSS_31") (pintype "power_in"))
      (node (ref "IC1") (pin "36") (pinfunction "VSS2_36") (pintype "power_in"))
      (node (ref "IC1") (pin "45") (pinfunction "VSS3_45") (pintype "power_in"))
      (node (ref "IC1") (pin "65") (pinfunction "VSS_65") (pintype "power_in"))
      (node (ref "IC1") (pin "75") (pinfunction "VSS4_75") (pintype "power_in"))
      (node (ref "IC2") (pin "10") (pinfunction "GND_10") (pintype "bidirectional"))
      (node (ref "IC3") (pin "4") (pinfunction "VSS_4") (pintype "input"))
      (node (ref "IC4") (pin "4") (pinfunction "VSS_4") (pintype "bidirectional"))
      (node (ref "IC5") (pin "2") (pinfunction "VSS_2") (pintype "power_in"))
      (node (ref "JP1") (pin "14") (pinfunction "14_14") (pintype "passive"))
      (node (ref "JP1") (pin "15") (pinfunction "15_15") (pintype "passive"))
      (node (ref "JP2") (pin "3") (pinfunction "3_3") (pintype "passive"))
      (node (ref "JP5") (pin "3") (pinfunction "3_3") (pintype "passive"))
      (node (ref "JP6") (pin "5") (pinfunction "5_5") (pintype "passive"))
      (node (ref "JP7") (pin "3") (pinfunction "3_3") (pintype "passive"))
      (node (ref "JP8") (pin "2") (pinfunction "2_2") (pintype "passive"))
      (node (ref "LED1") (pin "C") (pinfunction "C_C") (pintype "passive"))
      (node (ref "LED2") (pin "C") (pinfunction "C_C") (pintype "passive"))
      (node (ref "LED3") (pin "C") (pinfunction "C_C") (pintype "passive"))
      (node (ref "LED4") (pin "C") (pinfunction "C_C") (pintype "passive"))
      (node (ref "LED5") (pin "C") (pinfunction "C_C") (pintype "passive"))
      (node (ref "R15") (pin "1") (pinfunction "1_1") (pintype "passive"))
      (node (ref "R26") (pin "1") (pinfunction "1_1") (pintype "passive"))
      (node (ref "R27") (pin "1") (pinfunction "1_1") (pintype "passive"))
      (node (ref "R28") (pin "1") (pinfunction "1_1") (pintype "passive"))
      (node (ref "R29") (pin "1") (pinfunction "1_1") (pintype "passive"))
      (node (ref "R30") (pin "1") (pinfunction "1_1") (pintype "passive"))
      (node (ref "RN4") (pin "8") (pinfunction "8_8") (pintype "passive"))
      (node (ref "SD1") (pin "6") (pinfunction "GND_6") (pintype "power_in"))
      (node (ref "SD2") (pin "6") (pinfunction "GND_6") (pintype "power_in"))
      (node (ref "U$1") (pin "3") (pinfunction "A_3") (pintype "bidirectional"))
      (node (ref "U$2") (pin "13") (pinfunction "GND_13") (pintype "bidirectional"))
      (node (ref "U$8") (pin "1") (pinfunction "P$2_1") (pintype "bidirectional"))
      (node (ref "U2") (pin "12") (pinfunction "VSSQ_12") (pintype "power_in"))
      (node (ref "U2") (pin "28") (pinfunction "VSS_28") (pintype "power_in"))
      (node (ref "U2") (pin "41") (pinfunction "VSS_41") (pintype "power_in"))
      (node (ref "U2") (pin "46") (pinfunction "VSSQ_46") (pintype "power_in"))
      (node (ref "U2") (pin "52") (pinfunction "VSSQ_52") (pintype "power_in"))
      (node (ref "U2") (pin "54") (pinfunction "VSS_54") (pintype "power_in"))
      (node (ref "U2") (pin "6") (pinfunction "VSSQ_6") (pintype "power_in"))
      (node (ref "USB1") (pin "GND") (pinfunction "GND_GND") (pintype "bidirectional"))
    )
    (net (code "87") (name "Net-(1-IO1_)") (class "Default")
      (node (ref "1") (pin "1") (pinfunction "IO1__1") (pintype "bidirectional"))
      (node (ref "USB1") (pin "D-") (pinfunction "D-_D-") (pintype "bidirectional"))
    )
    (net (code "88") (name "Net-(1-IO2_)") (class "Default")
      (node (ref "1") (pin "3") (pinfunction "IO2__3") (pintype "bidirectional"))
      (node (ref "USB1") (pin "D+") (pinfunction "D+_D+") (pintype "bidirectional"))
    )
    (net (code "89") (name "Net-(C15-Pad2)") (class "Default")
      (node (ref "C15") (pin "2") (pinfunction "2_2") (pintype "passive"))
      (node (ref "R15") (pin "2") (pinfunction "2_2") (pintype "passive"))
      (node (ref "USB1") (pin "GND@1") (pinfunction "GND_GND@1") (pintype "bidirectional"))
      (node (ref "USB1") (pin "GND@3") (pinfunction "GND_GND@3") (pintype "bidirectional"))
    )
    (net (code "90") (name "Net-(D2-PadA)") (class "Default")
      (node (ref "D2") (pin "A") (pinfunction "A_A") (pintype "input"))
      (node (ref "JP1") (pin "13") (pinfunction "13_13") (pintype "passive"))
    )
    (net (code "91") (name "Net-(IC1-RC12{slash}OSC1{slash}CLKI)") (class "Default")
      (node (ref "C9") (pin "1") (pinfunction "1_1") (pintype "passive"))
      (node (ref "IC1") (pin "63") (pinfunction "RC12/OSC1/CLKI_63") (pintype "bidirectional"))
      (node (ref "X2") (pin "P$2") (pinfunction "P$2_P$2") (pintype "bidirectional"))
    )
    (net (code "92") (name "Net-(IC1-RC15{slash}OSC2{slash}CLKO)") (class "Default")
      (node (ref "C8") (pin "1") (pinfunction "1_1") (pintype "passive"))
      (node (ref "IC1") (pin "64") (pinfunction "RC15/OSC2/CLKO_64") (pintype "bidirectional"))
      (node (ref "X2") (pin "P$1") (pinfunction "P$1_P$1") (pintype "bidirectional"))
    )
    (net (code "93") (name "Net-(IC1-VCAP)") (class "Default")
      (node (ref "C7") (pin "1") (pinfunction "1_1") (pintype "passive"))
      (node (ref "IC1") (pin "85") (pinfunction "VCAP_85") (pintype "bidirectional"))
    )
    (net (code "94") (name "Net-(IC2-1A4)") (class "Default")
      (node (ref "IC2") (pin "8") (pinfunction "1A4_8") (pintype "bidirectional"))
      (node (ref "R8") (pin "2") (pinfunction "2_2") (pintype "passive"))
      (node (ref "SD1") (pin "7") (pinfunction "DO_7") (pintype "bidirectional"))
    )
    (net (code "95") (name "Net-(IC2-1Y1)") (class "Default")
      (node (ref "IC2") (pin "18") (pinfunction "1Y1_18") (pintype "bidirectional"))
      (node (ref "R27") (pin "2") (pinfunction "2_2") (pintype "passive"))
      (node (ref "SD1") (pin "5") (pinfunction "CLK_5") (pintype "bidirectional"))
    )
    (net (code "96") (name "Net-(IC2-1Y2)") (class "Default")
      (node (ref "IC2") (pin "16") (pinfunction "1Y2_16") (pintype "bidirectional"))
      (node (ref "R25") (pin "2") (pinfunction "2_2") (pintype "passive"))
      (node (ref "SD1") (pin "3") (pinfunction "DI_3") (pintype "bidirectional"))
    )
    (net (code "97") (name "Net-(IC2-1Y3)") (class "Default")
      (node (ref "IC2") (pin "14") (pinfunction "1Y3_14") (pintype "bidirectional"))
      (node (ref "R22") (pin "1") (pinfunction "1_1") (pintype "passive"))
      (node (ref "SD1") (pin "2") (pinfunction "CS_2") (pintype "bidirectional"))
    )
    (net (code "98") (name "Net-(IC2-2A4)") (class "Default")
      (node (ref "IC2") (pin "17") (pinfunction "2A4_17") (pintype "bidirectional"))
      (node (ref "R11") (pin "1") (pinfunction "1_1") (pintype "passive"))
      (node (ref "SD2") (pin "7") (pinfunction "DO_7") (pintype "bidirectional"))
    )
    (net (code "99") (name "Net-(IC2-2Y1)") (class "Default")
      (node (ref "IC2") (pin "9") (pinfunction "2Y1_9") (pintype "bidirectional"))
      (node (ref "R26") (pin "2") (pinfunction "2_2") (pintype "passive"))
      (node (ref "SD2") (pin "5") (pinfunction "CLK_5") (pintype "bidirectional"))
    )
    (net (code "100") (name "Net-(IC2-2Y2)") (class "Default")
      (node (ref "IC2") (pin "7") (pinfunction "2Y2_7") (pintype "bidirectional"))
      (node (ref "R24") (pin "1") (pinfunction "1_1") (pintype "passive"))
      (node (ref "SD2") (pin "3") (pinfunction "DI_3") (pintype "bidirectional"))
    )
    (net (code "101") (name "Net-(IC2-2Y3)") (class "Default")
      (node (ref "IC2") (pin "5") (pinfunction "2Y3_5") (pintype "bidirectional"))
      (node (ref "R23") (pin "1") (pinfunction "1_1") (pintype "passive"))
      (node (ref "SD2") (pin "2") (pinfunction "CS_2") (pintype "bidirectional"))
    )
    (net (code "102") (name "Net-(IC4-OSCI)") (class "Default")
      (node (ref "C12") (pin "1") (pinfunction "1_1") (pintype "passive"))
      (node (ref "IC4") (pin "1") (pinfunction "OSCI_1") (pintype "bidirectional"))
      (node (ref "X1") (pin "P$2") (pinfunction "P$2_P$2") (pintype "bidirectional"))
    )
    (net (code "103") (name "Net-(IC4-OSCO)") (class "Default")
      (node (ref "IC4") (pin "2") (pinfunction "OSCO_2") (pintype "bidirectional"))
      (node (ref "X1") (pin "P$1") (pinfunction "P$1_P$1") (pintype "bidirectional"))
    )
    (net (code "104") (name "Net-(IC4-VDD)") (class "Default")
      (node (ref "C13") (pin "1") (pinfunction "1_1") (pintype "passive"))
      (node (ref "IC4") (pin "8") (pinfunction "VDD_8") (pintype "bidirectional"))
      (node (ref "U$6") (pin "3") (pinfunction "C_3") (pintype "bidirectional"))
    )
    (net (code "105") (name "Net-(JP3-Pad4)") (class "Default")
      (node (ref "JP3") (pin "4") (pinfunction "4_4") (pintype "passive"))
      (node (ref "R14") (pin "2") (pinfunction "2_2") (pintype "passive"))
    )
    (net (code "106") (name "Net-(JP6-Pad6)") (class "Default")
      (node (ref "JP6") (pin "6") (pinfunction "6_6") (pintype "passive"))
      (node (ref "R19") (pin "2") (pinfunction "2_2") (pintype "passive"))
    )
    (net (code "107") (name "Net-(LED1-PadA)") (class "Default")
      (node (ref "LED1") (pin "A") (pinfunction "A_A") (pintype "passive"))
      (node (ref "R2") (pin "2") (pinfunction "2_2") (pintype "passive"))
    )
    (net (code "108") (name "Net-(LED2-PadA)") (class "Default")
      (node (ref "LED2") (pin "A") (pinfunction "A_A") (pintype "passive"))
      (node (ref "R3") (pin "2") (pinfunction "2_2") (pintype "passive"))
    )
    (net (code "109") (name "Net-(LED3-PadA)") (class "Default")
      (node (ref "LED3") (pin "A") (pinfunction "A_A") (pintype "passive"))
      (node (ref "R4") (pin "2") (pinfunction "2_2") (pintype "passive"))
    )
    (net (code "110") (name "Net-(LED4-PadA)") (class "Default")
      (node (ref "LED4") (pin "A") (pinfunction "A_A") (pintype "passive"))
      (node (ref "R5") (pin "2") (pinfunction "2_2") (pintype "passive"))
    )
    (net (code "111") (name "Net-(LED5-PadA)") (class "Default")
      (node (ref "LED5") (pin "A") (pinfunction "A_A") (pintype "passive"))
      (node (ref "R21") (pin "2") (pinfunction "2_2") (pintype "passive"))
    )
    (net (code "112") (name "Net-(SD1-VCC)") (class "Default")
      (node (ref "C6") (pin "1") (pinfunction "1_1") (pintype "passive"))
      (node (ref "R22") (pin "2") (pinfunction "2_2") (pintype "passive"))
      (node (ref "R25") (pin "1") (pinfunction "1_1") (pintype "passive"))
      (node (ref "R29") (pin "2") (pinfunction "2_2") (pintype "passive"))
      (node (ref "R8") (pin "1") (pinfunction "1_1") (pintype "passive"))
      (node (ref "SD1") (pin "4") (pinfunction "VCC_4") (pintype "passive"))
      (node (ref "U$12") (pin "3") (pinfunction "D_3") (pintype "passive"))
    )
    (net (code "113") (name "Net-(SD2-VCC)") (class "Default")
      (node (ref "C16") (pin "1") (pinfunction "1_1") (pintype "passive"))
      (node (ref "R11") (pin "2") (pinfunction "2_2") (pintype "passive"))
      (node (ref "R23") (pin "2") (pinfunction "2_2") (pintype "passive"))
      (node (ref "R24") (pin "2") (pinfunction "2_2") (pintype "passive"))
      (node (ref "R28") (pin "2") (pinfunction "2_2") (pintype "passive"))
      (node (ref "SD2") (pin "4") (pinfunction "VCC_4") (pintype "passive"))
      (node (ref "T1") (pin "3") (pinfunction "D_3") (pintype "passive"))
    )
    (net (code "114") (name "Net-(U$2-BAT)") (class "Default")
      (node (ref "B1") (pin "POS2") (pinfunction "POS2_POS2") (pintype "bidirectional"))
      (node (ref "C2") (pin "1") (pinfunction "1_1") (pintype "passive"))
      (node (ref "U$2") (pin "14") (pinfunction "BAT_14") (pintype "bidirectional"))
      (node (ref "U$6") (pin "2") (pinfunction "A2_2") (pintype "bidirectional"))
    )
    (net (code "115") (name "Net-(U$8-P$1)") (class "Default")
      (node (ref "R18") (pin "2") (pinfunction "2_2") (pintype "passive"))
      (node (ref "U$8") (pin "2") (pinfunction "P$1_2") (pintype "bidirectional"))
    )
    (net (code "116") (name "Net-(U2-CAS#)") (class "Default")
      (node (ref "RN3") (pin "3") (pinfunction "3_3") (pintype "passive"))
      (node (ref "U2") (pin "17") (pinfunction "CAS#_17") (pintype "input"))
    )
    (net (code "117") (name "Net-(U2-CLK)") (class "Default")
      (node (ref "R17") (pin "1") (pinfunction "1_1") (pintype "passive"))
      (node (ref "U2") (pin "38") (pinfunction "CLK_38") (pintype "input"))
    )
    (net (code "118") (name "Net-(U2-CS#)") (class "Default")
      (node (ref "RN3") (pin "1") (pinfunction "1_1") (pintype "passive"))
      (node (ref "U2") (pin "19") (pinfunction "CS#_19") (pintype "input"))
    )
    (net (code "119") (name "Net-(U2-DQ0)") (class "Default")
      (node (ref "RN1") (pin "8") (pinfunction "8_8") (pintype "passive"))
      (node (ref "U2") (pin "2") (pinfunction "DQ0_2") (pintype "bidirectional"))
      (node (ref "U2") (pin "53") (pinfunction "DQ15_53") (pintype "bidirectional"))
    )
    (net (code "120") (name "Net-(U2-DQ1)") (class "Default")
      (node (ref "RN1") (pin "7") (pinfunction "7_7") (pintype "passive"))
      (node (ref "U2") (pin "4") (pinfunction "DQ1_4") (pintype "bidirectional"))
      (node (ref "U2") (pin "51") (pinfunction "DQ14_51") (pintype "bidirectional"))
    )
    (net (code "121") (name "Net-(U2-DQ6)") (class "Default")
      (node (ref "RN2") (pin "6") (pinfunction "6_6") (pintype "passive"))
      (node (ref "U2") (pin "11") (pinfunction "DQ6_11") (pintype "bidirectional"))
      (node (ref "U2") (pin "44") (pinfunction "DQ9_44") (pintype "bidirectional"))
    )
    (net (code "122") (name "Net-(U2-DQ7)") (class "Default")
      (node (ref "RN2") (pin "5") (pinfunction "5_5") (pintype "passive"))
      (node (ref "U2") (pin "13") (pinfunction "DQ7_13") (pintype "bidirectional"))
      (node (ref "U2") (pin "42") (pinfunction "DQ8_42") (pintype "bidirectional"))
    )
    (net (code "123") (name "Net-(U2-DQ10)") (class "Default")
      (node (ref "RN2") (pin "7") (pinfunction "7_7") (pintype "passive"))
      (node (ref "U2") (pin "10") (pinfunction "DQ5_10") (pintype "bidirectional"))
      (node (ref "U2") (pin "45") (pinfunction "DQ10_45") (pintype "bidirectional"))
    )
    (net (code "124") (name "Net-(U2-DQ11)") (class "Default")
      (node (ref "RN2") (pin "8") (pinfunction "8_8") (pintype "passive"))
      (node (ref "U2") (pin "47") (pinfunction "DQ11_47") (pintype "bidirectional"))
      (node (ref "U2") (pin "8") (pinfunction "DQ4_8") (pintype "bidirectional"))
    )
    (net (code "125") (name "Net-(U2-DQ12)") (class "Default")
      (node (ref "RN1") (pin "5") (pinfunction "5_5") (pintype "passive"))
      (node (ref "U2") (pin "48") (pinfunction "DQ12_48") (pintype "bidirectional"))
      (node (ref "U2") (pin "7") (pinfunction "DQ3_7") (pintype "bidirectional"))
    )
    (net (code "126") (name "Net-(U2-DQ13)") (class "Default")
      (node (ref "RN1") (pin "6") (pinfunction "6_6") (pintype "passive"))
      (node (ref "U2") (pin "5") (pinfunction "DQ2_5") (pintype "bidirectional"))
      (node (ref "U2") (pin "50") (pinfunction "DQ13_50") (pintype "bidirectional"))
    )
    (net (code "127") (name "Net-(U2-RAS#)") (class "Default")
      (node (ref "RN3") (pin "2") (pinfunction "2_2") (pintype "passive"))
      (node (ref "U2") (pin "18") (pinfunction "RAS#_18") (pintype "input"))
    )
    (net (code "128") (name "Net-(U2-WE#)") (class "Default")
      (node (ref "RN3") (pin "4") (pinfunction "4_4") (pintype "passive"))
      (node (ref "U2") (pin "16") (pinfunction "WE#_16") (pintype "input"))
    )
    (net (code "129") (name "unconnected-(B1-PadPOS1)") (class "Default")
      (node (ref "B1") (pin "POS1") (pinfunction "POS1_POS1") (pintype "bidirectional"))
    )
    (net (code "130") (name "unconnected-(IC4-CO-Pad7)") (class "Default")
      (node (ref "IC4") (pin "7") (pinfunction "CO_7") (pintype "bidirectional"))
    )
    (net (code "131") (name "unconnected-(IC4-INT-Pad3)") (class "Default")
      (node (ref "IC4") (pin "3") (pinfunction "INT_3") (pintype "bidirectional"))
    )
    (net (code "132") (name "unconnected-(IC5-ALERT-Pad3)") (class "Default")
      (node (ref "IC5") (pin "3") (pinfunction "ALERT_3") (pintype "bidirectional"))
    )
    (net (code "133") (name "unconnected-(U$2-32K-Pad1)") (class "Default")
      (node (ref "U$2") (pin "1") (pinfunction "32K_1") (pintype "bidirectional"))
    )
    (net (code "134") (name "unconnected-(U$2-~{INT}-Pad3)") (class "Default")
      (node (ref "U$2") (pin "3") (pinfunction "~{INT}_3") (pintype "bidirectional"))
    )
    (net (code "135") (name "unconnected-(U$2-~{RST}-Pad4)") (class "Default")
      (node (ref "U$2") (pin "4") (pinfunction "~{RST}_4") (pintype "bidirectional"))
    )
    (net (code "136") (name "unconnected-(U2-NC-Pad40)") (class "Default")
      (node (ref "U2") (pin "40") (pinfunction "NC_40") (pintype "no_connect"))
    )
  )
)
